# pinoccio-proto.net
KiCad netlist of a schematic drawn in EAGLE
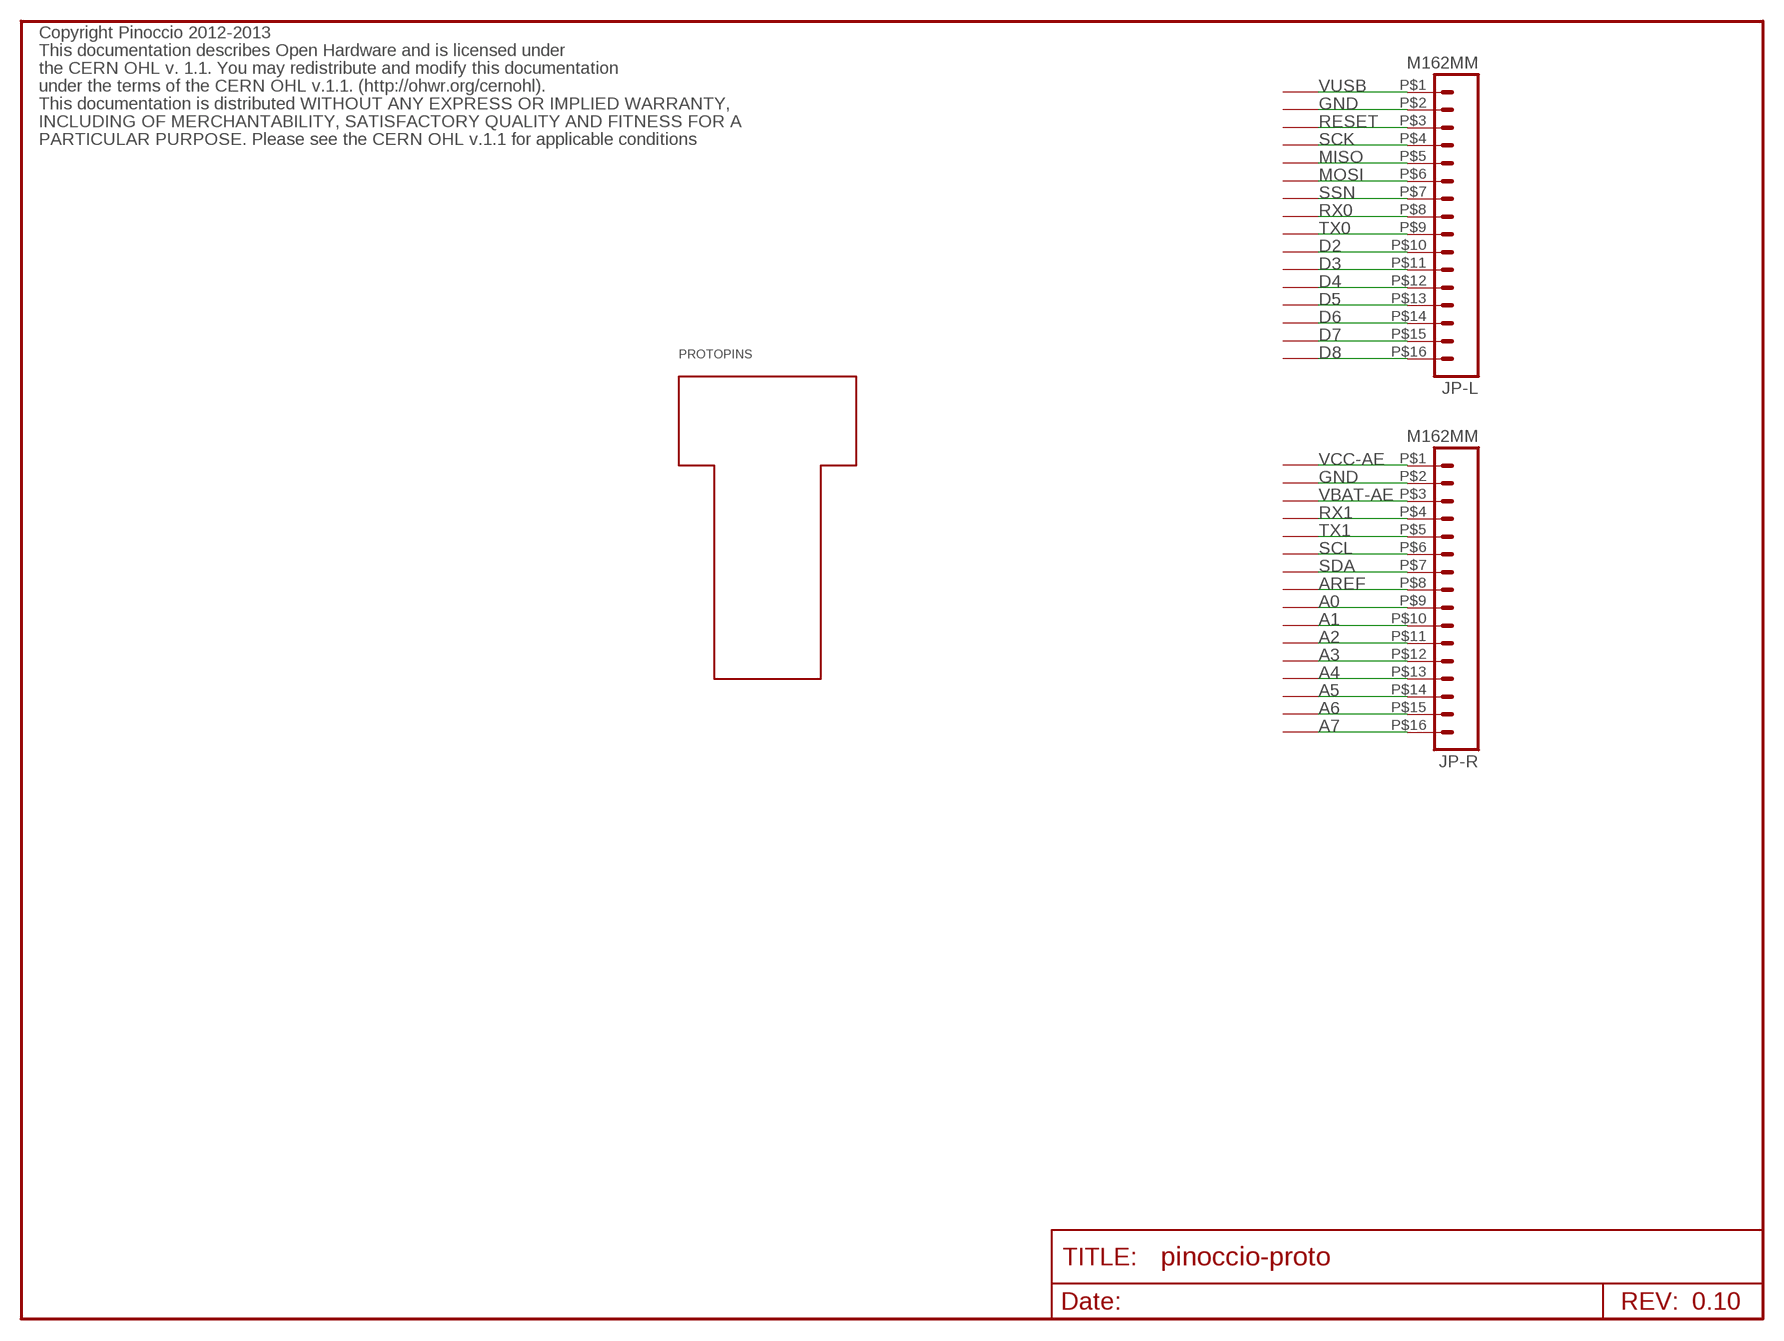
[diagram p0: schematic, sheet 1]

(export (version "E")
  (design (tool "Eeschema 10.0.6"))
  (components
    (comp (ref "JP-L")
      (value "M162MM")
      (footprint "eagle-import:1X16_2MM")
      (libsource (lib "eagle-import") (part "M162MM"))
    )
    (comp (ref "JP-R")
      (value "M162MM")
      (footprint "eagle-import:1X16_2MM")
      (libsource (lib "eagle-import") (part "M162MM"))
    )
    (comp (ref "PROTOPINS")
      (value "PROTO")
      (footprint "eagle-import:1X1PROTO")
      (libsource (lib "eagle-import") (part "PROTO"))
    )
    (comp (ref "U$2")
      (value "PAD55-RRECT")
      (footprint "eagle-import:PAD-100X55-RRECT")
      (libsource (lib "eagle-import") (part "PAD55-RRECT"))
    )
    (comp (ref "U$3")
      (value "PAD55-RRECT")
      (footprint "eagle-import:PAD-100X55-RRECT")
      (libsource (lib "eagle-import") (part "PAD55-RRECT"))
    )
    (comp (ref "U$4")
      (value "PAD55-RRECT")
      (footprint "eagle-import:PAD-100X55-RRECT")
      (libsource (lib "eagle-import") (part "PAD55-RRECT"))
    )
    (comp (ref "U$5")
      (value "PAD55-RRECT")
      (footprint "eagle-import:PAD-100X55-RRECT")
      (libsource (lib "eagle-import") (part "PAD55-RRECT"))
    )
    (comp (ref "U$6")
      (value "PAD55-RRECT")
      (footprint "eagle-import:PAD-100X55-RRECT")
      (libsource (lib "eagle-import") (part "PAD55-RRECT"))
    )
    (comp (ref "U$7")
      (value "PAD55-RRECT")
      (footprint "eagle-import:PAD-100X55-RRECT")
      (libsource (lib "eagle-import") (part "PAD55-RRECT"))
    )
    (comp (ref "U$8")
      (value "PAD55-RRECT")
      (footprint "eagle-import:PAD-100X55-RRECT")
      (libsource (lib "eagle-import") (part "PAD55-RRECT"))
    )
    (comp (ref "U$9")
      (value "PAD55-RRECT")
      (footprint "eagle-import:PAD-100X55-RRECT")
      (libsource (lib "eagle-import") (part "PAD55-RRECT"))
    )
    (comp (ref "U$10")
      (value "PAD55-RRECT")
      (footprint "eagle-import:PAD-100X55-RRECT")
      (libsource (lib "eagle-import") (part "PAD55-RRECT"))
    )
    (comp (ref "U$11")
      (value "PAD55-RRECT")
      (footprint "eagle-import:PAD-100X55-RRECT")
      (libsource (lib "eagle-import") (part "PAD55-RRECT"))
    )
    (comp (ref "U$12")
      (value "PAD55-RRECT")
      (footprint "eagle-import:PAD-100X55-RRECT")
      (libsource (lib "eagle-import") (part "PAD55-RRECT"))
    )
    (comp (ref "U$13")
      (value "PAD55-RRECT")
      (footprint "eagle-import:PAD-100X55-RRECT")
      (libsource (lib "eagle-import") (part "PAD55-RRECT"))
    )
    (comp (ref "U$14")
      (value "PAD55-RRECT")
      (footprint "eagle-import:PAD-100X55-RRECT")
      (libsource (lib "eagle-import") (part "PAD55-RRECT"))
    )
    (comp (ref "U$15")
      (value "PAD55-RRECT")
      (footprint "eagle-import:PAD-100X55-RRECT")
      (libsource (lib "eagle-import") (part "PAD55-RRECT"))
    )
    (comp (ref "U$16")
      (value "PAD55-RRECT")
      (footprint "eagle-import:PAD-100X55-RRECT")
      (libsource (lib "eagle-import") (part "PAD55-RRECT"))
    )
    (comp (ref "U$17")
      (value "PAD55-RRECT")
      (footprint "eagle-import:PAD-100X55-RRECT")
      (libsource (lib "eagle-import") (part "PAD55-RRECT"))
    )
    (comp (ref "U$18")
      (value "PAD55-RRECT")
      (footprint "eagle-import:PAD-100X55-RRECT")
      (libsource (lib "eagle-import") (part "PAD55-RRECT"))
    )
    (comp (ref "U$19")
      (value "PAD55-RRECT")
      (footprint "eagle-import:PAD-100X55-RRECT")
      (libsource (lib "eagle-import") (part "PAD55-RRECT"))
    )
    (comp (ref "U$20")
      (value "PAD55-RRECT")
      (footprint "eagle-import:PAD-100X55-RRECT")
      (libsource (lib "eagle-import") (part "PAD55-RRECT"))
    )
    (comp (ref "U$21")
      (value "PAD55-RRECT")
      (footprint "eagle-import:PAD-100X55-RRECT")
      (libsource (lib "eagle-import") (part "PAD55-RRECT"))
    )
    (comp (ref "U$22")
      (value "PAD55-RRECT")
      (footprint "eagle-import:PAD-100X55-RRECT")
      (libsource (lib "eagle-import") (part "PAD55-RRECT"))
    )
    (comp (ref "U$23")
      (value "PAD55-RRECT")
      (footprint "eagle-import:PAD-100X55-RRECT")
      (libsource (lib "eagle-import") (part "PAD55-RRECT"))
    )
    (comp (ref "U$24")
      (value "PAD55-RRECT")
      (footprint "eagle-import:PAD-100X55-RRECT")
      (libsource (lib "eagle-import") (part "PAD55-RRECT"))
    )
    (comp (ref "U$25")
      (value "PAD55-RRECT")
      (footprint "eagle-import:PAD-100X55-RRECT")
      (libsource (lib "eagle-import") (part "PAD55-RRECT"))
    )
    (comp (ref "U$26")
      (value "PAD55-RRECT")
      (footprint "eagle-import:PAD-100X55-RRECT")
      (libsource (lib "eagle-import") (part "PAD55-RRECT"))
    )
    (comp (ref "U$27")
      (value "PAD55-RRECT")
      (footprint "eagle-import:PAD-100X55-RRECT")
      (libsource (lib "eagle-import") (part "PAD55-RRECT"))
    )
    (comp (ref "U$28")
      (value "PAD55-RRECT")
      (footprint "eagle-import:PAD-100X55-RRECT")
      (libsource (lib "eagle-import") (part "PAD55-RRECT"))
    )
    (comp (ref "U$29")
      (value "PAD55-RRECT")
      (footprint "eagle-import:PAD-100X55-RRECT")
      (libsource (lib "eagle-import") (part "PAD55-RRECT"))
    )
    (comp (ref "U$30")
      (value "PAD55-RRECT")
      (footprint "eagle-import:PAD-100X55-RRECT")
      (libsource (lib "eagle-import") (part "PAD55-RRECT"))
    )
    (comp (ref "U$31")
      (value "PAD55-RRECT")
      (footprint "eagle-import:PAD-100X55-RRECT")
      (libsource (lib "eagle-import") (part "PAD55-RRECT"))
    )
    (comp (ref "U$32")
      (value "PAD55-RRECT")
      (footprint "eagle-import:PAD-100X55-RRECT")
      (libsource (lib "eagle-import") (part "PAD55-RRECT"))
    )
    (comp (ref "U$33")
      (value "PAD55-RRECT")
      (footprint "eagle-import:PAD-100X55-RRECT")
      (libsource (lib "eagle-import") (part "PAD55-RRECT"))
    )
  )
  (nets
    (net (code "1") (name "/A0") (class "Default")
      (node (ref "JP-R") (pin "P$9") (pinfunction "9_P$9") (pintype "passive"))
      (node (ref "U$25") (pin "P$1") (pinfunction "P$1_P$1") (pintype "bidirectional"))
    )
    (net (code "2") (name "/A1") (class "Default")
      (node (ref "JP-R") (pin "P$10") (pinfunction "10_P$10") (pintype "passive"))
      (node (ref "U$24") (pin "P$1") (pinfunction "P$1_P$1") (pintype "bidirectional"))
    )
    (net (code "3") (name "/A2") (class "Default")
      (node (ref "JP-R") (pin "P$11") (pinfunction "11_P$11") (pintype "passive"))
      (node (ref "U$23") (pin "P$1") (pinfunction "P$1_P$1") (pintype "bidirectional"))
    )
    (net (code "4") (name "/A3") (class "Default")
      (node (ref "JP-R") (pin "P$12") (pinfunction "12_P$12") (pintype "passive"))
      (node (ref "U$22") (pin "P$1") (pinfunction "P$1_P$1") (pintype "bidirectional"))
    )
    (net (code "5") (name "/A4") (class "Default")
      (node (ref "JP-R") (pin "P$13") (pinfunction "13_P$13") (pintype "passive"))
      (node (ref "U$21") (pin "P$1") (pinfunction "P$1_P$1") (pintype "bidirectional"))
    )
    (net (code "6") (name "/A5") (class "Default")
      (node (ref "JP-R") (pin "P$14") (pinfunction "14_P$14") (pintype "passive"))
      (node (ref "U$20") (pin "P$1") (pinfunction "P$1_P$1") (pintype "bidirectional"))
    )
    (net (code "7") (name "/A6") (class "Default")
      (node (ref "JP-R") (pin "P$15") (pinfunction "15_P$15") (pintype "passive"))
      (node (ref "U$19") (pin "P$1") (pinfunction "P$1_P$1") (pintype "bidirectional"))
    )
    (net (code "8") (name "/A7") (class "Default")
      (node (ref "JP-R") (pin "P$16") (pinfunction "16_P$16") (pintype "passive"))
      (node (ref "U$18") (pin "P$1") (pinfunction "P$1_P$1") (pintype "bidirectional"))
    )
    (net (code "9") (name "/AREF") (class "Default")
      (node (ref "JP-R") (pin "P$8") (pinfunction "8_P$8") (pintype "passive"))
      (node (ref "U$26") (pin "P$1") (pinfunction "P$1_P$1") (pintype "bidirectional"))
    )
    (net (code "10") (name "/D2") (class "Default")
      (node (ref "JP-L") (pin "P$10") (pinfunction "10_P$10") (pintype "passive"))
      (node (ref "U$7") (pin "P$1") (pinfunction "P$1_P$1") (pintype "bidirectional"))
    )
    (net (code "11") (name "/D3") (class "Default")
      (node (ref "JP-L") (pin "P$11") (pinfunction "11_P$11") (pintype "passive"))
      (node (ref "U$6") (pin "P$1") (pinfunction "P$1_P$1") (pintype "bidirectional"))
    )
    (net (code "12") (name "/D4") (class "Default")
      (node (ref "JP-L") (pin "P$12") (pinfunction "12_P$12") (pintype "passive"))
      (node (ref "U$5") (pin "P$1") (pinfunction "P$1_P$1") (pintype "bidirectional"))
    )
    (net (code "13") (name "/D5") (class "Default")
      (node (ref "JP-L") (pin "P$13") (pinfunction "13_P$13") (pintype "passive"))
      (node (ref "U$3") (pin "P$1") (pinfunction "P$1_P$1") (pintype "bidirectional"))
    )
    (net (code "14") (name "/D6") (class "Default")
      (node (ref "JP-L") (pin "P$14") (pinfunction "14_P$14") (pintype "passive"))
      (node (ref "U$4") (pin "P$1") (pinfunction "P$1_P$1") (pintype "bidirectional"))
    )
    (net (code "15") (name "/D7") (class "Default")
      (node (ref "JP-L") (pin "P$15") (pinfunction "15_P$15") (pintype "passive"))
      (node (ref "U$2") (pin "P$1") (pinfunction "P$1_P$1") (pintype "bidirectional"))
    )
    (net (code "16") (name "/D8") (class "Default")
      (node (ref "JP-L") (pin "P$16") (pinfunction "16_P$16") (pintype "passive"))
      (node (ref "U$17") (pin "P$1") (pinfunction "P$1_P$1") (pintype "bidirectional"))
    )
    (net (code "17") (name "/GND") (class "Default")
      (node (ref "JP-L") (pin "P$2") (pinfunction "2_P$2") (pintype "passive"))
      (node (ref "JP-R") (pin "P$2") (pinfunction "2_P$2") (pintype "passive"))
      (node (ref "U$15") (pin "P$1") (pinfunction "P$1_P$1") (pintype "bidirectional"))
      (node (ref "U$32") (pin "P$1") (pinfunction "P$1_P$1") (pintype "bidirectional"))
    )
    (net (code "18") (name "/MISO") (class "Default")
      (node (ref "JP-L") (pin "P$5") (pinfunction "5_P$5") (pintype "passive"))
      (node (ref "U$12") (pin "P$1") (pinfunction "P$1_P$1") (pintype "bidirectional"))
    )
    (net (code "19") (name "/MOSI") (class "Default")
      (node (ref "JP-L") (pin "P$6") (pinfunction "6_P$6") (pintype "passive"))
      (node (ref "U$11") (pin "P$1") (pinfunction "P$1_P$1") (pintype "bidirectional"))
    )
    (net (code "20") (name "/RESET") (class "Default")
      (node (ref "JP-L") (pin "P$3") (pinfunction "3_P$3") (pintype "passive"))
      (node (ref "U$14") (pin "P$1") (pinfunction "P$1_P$1") (pintype "bidirectional"))
    )
    (net (code "21") (name "/RX0") (class "Default")
      (node (ref "JP-L") (pin "P$8") (pinfunction "8_P$8") (pintype "passive"))
      (node (ref "U$9") (pin "P$1") (pinfunction "P$1_P$1") (pintype "bidirectional"))
    )
    (net (code "22") (name "/RX1") (class "Default")
      (node (ref "JP-R") (pin "P$4") (pinfunction "4_P$4") (pintype "passive"))
      (node (ref "U$30") (pin "P$1") (pinfunction "P$1_P$1") (pintype "bidirectional"))
    )
    (net (code "23") (name "/SCK") (class "Default")
      (node (ref "JP-L") (pin "P$4") (pinfunction "4_P$4") (pintype "passive"))
      (node (ref "U$13") (pin "P$1") (pinfunction "P$1_P$1") (pintype "bidirectional"))
    )
    (net (code "24") (name "/SCL") (class "Default")
      (node (ref "JP-R") (pin "P$6") (pinfunction "6_P$6") (pintype "passive"))
      (node (ref "U$28") (pin "P$1") (pinfunction "P$1_P$1") (pintype "bidirectional"))
    )
    (net (code "25") (name "/SDA") (class "Default")
      (node (ref "JP-R") (pin "P$7") (pinfunction "7_P$7") (pintype "passive"))
      (node (ref "U$27") (pin "P$1") (pinfunction "P$1_P$1") (pintype "bidirectional"))
    )
    (net (code "26") (name "/SSN") (class "Default")
      (node (ref "JP-L") (pin "P$7") (pinfunction "7_P$7") (pintype "passive"))
      (node (ref "U$10") (pin "P$1") (pinfunction "P$1_P$1") (pintype "bidirectional"))
    )
    (net (code "27") (name "/TX0") (class "Default")
      (node (ref "JP-L") (pin "P$9") (pinfunction "9_P$9") (pintype "passive"))
      (node (ref "U$8") (pin "P$1") (pinfunction "P$1_P$1") (pintype "bidirectional"))
    )
    (net (code "28") (name "/TX1") (class "Default")
      (node (ref "JP-R") (pin "P$5") (pinfunction "5_P$5") (pintype "passive"))
      (node (ref "U$29") (pin "P$1") (pinfunction "P$1_P$1") (pintype "bidirectional"))
    )
    (net (code "29") (name "/VBAT-AE") (class "Default")
      (node (ref "JP-R") (pin "P$3") (pinfunction "3_P$3") (pintype "passive"))
      (node (ref "U$31") (pin "P$1") (pinfunction "P$1_P$1") (pintype "bidirectional"))
    )
    (net (code "30") (name "/VCC-AE") (class "Default")
      (node (ref "JP-R") (pin "P$1") (pinfunction "1_P$1") (pintype "passive"))
      (node (ref "U$33") (pin "P$1") (pinfunction "P$1_P$1") (pintype "bidirectional"))
    )
    (net (code "31") (name "/VUSB") (class "Default")
      (node (ref "JP-L") (pin "P$1") (pinfunction "1_P$1") (pintype "passive"))
      (node (ref "U$16") (pin "P$1") (pinfunction "P$1_P$1") (pintype "bidirectional"))
    )
    (net (code "32") (name "unconnected-(PROTOPINS-P$1-Pad0)") (class "Default")
      (node (ref "PROTOPINS") (pin "0") (pinfunction "P$1_0") (pintype "bidirectional"))
    )
    (net (code "33") (name "unconnected-(PROTOPINS-P$2-Pad1)") (class "Default")
      (node (ref "PROTOPINS") (pin "1") (pinfunction "P$2_1") (pintype "bidirectional"))
    )
    (net (code "34") (name "unconnected-(PROTOPINS-P$3-Pad2)") (class "Default")
      (node (ref "PROTOPINS") (pin "2") (pinfunction "P$3_2") (pintype "bidirectional"))
    )
    (net (code "35") (name "unconnected-(PROTOPINS-P$4-Pad3)") (class "Default")
      (node (ref "PROTOPINS") (pin "3") (pinfunction "P$4_3") (pintype "bidirectional"))
    )
    (net (code "36") (name "unconnected-(PROTOPINS-P$5-Pad4)") (class "Default")
      (node (ref "PROTOPINS") (pin "4") (pinfunction "P$5_4") (pintype "bidirectional"))
    )
    (net (code "37") (name "unconnected-(PROTOPINS-P$6-Pad6)") (class "Default")
      (node (ref "PROTOPINS") (pin "6") (pinfunction "P$6_6") (pintype "bidirectional"))
    )
    (net (code "38") (name "unconnected-(PROTOPINS-P$7-Pad7)") (class "Default")
      (node (ref "PROTOPINS") (pin "7") (pinfunction "P$7_7") (pintype "bidirectional"))
    )
    (net (code "39") (name "unconnected-(PROTOPINS-P$8-Pad8)") (class "Default")
      (node (ref "PROTOPINS") (pin "8") (pinfunction "P$8_8") (pintype "bidirectional"))
    )
    (net (code "40") (name "unconnected-(PROTOPINS-P$9-Pad9)") (class "Default")
      (node (ref "PROTOPINS") (pin "9") (pinfunction "P$9_9") (pintype "bidirectional"))
    )
    (net (code "41") (name "unconnected-(PROTOPINS-P$10-Pad10)") (class "Default")
      (node (ref "PROTOPINS") (pin "10") (pinfunction "P$10_10") (pintype "bidirectional"))
    )
    (net (code "42") (name "unconnected-(PROTOPINS-P$11-Pad11)") (class "Default")
      (node (ref "PROTOPINS") (pin "11") (pinfunction "P$11_11") (pintype "bidirectional"))
    )
    (net (code "43") (name "unconnected-(PROTOPINS-P$12-Pad12)") (class "Default")
      (node (ref "PROTOPINS") (pin "12") (pinfunction "P$12_12") (pintype "bidirectional"))
    )
    (net (code "44") (name "unconnected-(PROTOPINS-P$13-Pad13)") (class "Default")
      (node (ref "PROTOPINS") (pin "13") (pinfunction "P$13_13") (pintype "bidirectional"))
    )
    (net (code "45") (name "unconnected-(PROTOPINS-P$14-Pad14)") (class "Default")
      (node (ref "PROTOPINS") (pin "14") (pinfunction "P$14_14") (pintype "bidirectional"))
    )
    (net (code "46") (name "unconnected-(PROTOPINS-P$15-Pad15)") (class "Default")
      (node (ref "PROTOPINS") (pin "15") (pinfunction "P$15_15") (pintype "bidirectional"))
    )
    (net (code "47") (name "unconnected-(PROTOPINS-P$16-Pad16)") (class "Default")
      (node (ref "PROTOPINS") (pin "16") (pinfunction "P$16_16") (pintype "bidirectional"))
    )
    (net (code "48") (name "unconnected-(PROTOPINS-P$17-Pad17)") (class "Default")
      (node (ref "PROTOPINS") (pin "17") (pinfunction "P$17_17") (pintype "bidirectional"))
    )
    (net (code "49") (name "unconnected-(PROTOPINS-P$18-Pad18)") (class "Default")
      (node (ref "PROTOPINS") (pin "18") (pinfunction "P$18_18") (pintype "bidirectional"))
    )
    (net (code "50") (name "unconnected-(PROTOPINS-P$19-Pad19)") (class "Default")
      (node (ref "PROTOPINS") (pin "19") (pinfunction "P$19_19") (pintype "bidirectional"))
    )
    (net (code "51") (name "unconnected-(PROTOPINS-P$20-Pad20)") (class "Default")
      (node (ref "PROTOPINS") (pin "20") (pinfunction "P$20_20") (pintype "bidirectional"))
    )
    (net (code "52") (name "unconnected-(PROTOPINS-P$21-Pad21)") (class "Default")
      (node (ref "PROTOPINS") (pin "21") (pinfunction "P$21_21") (pintype "bidirectional"))
    )
    (net (code "53") (name "unconnected-(PROTOPINS-P$22-Pad22)") (class "Default")
      (node (ref "PROTOPINS") (pin "22") (pinfunction "P$22_22") (pintype "bidirectional"))
    )
    (net (code "54") (name "unconnected-(PROTOPINS-P$23-Pad23)") (class "Default")
      (node (ref "PROTOPINS") (pin "23") (pinfunction "P$23_23") (pintype "bidirectional"))
    )
    (net (code "55") (name "unconnected-(PROTOPINS-P$24-Pad24)") (class "Default")
      (node (ref "PROTOPINS") (pin "24") (pinfunction "P$24_24") (pintype "bidirectional"))
    )
    (net (code "56") (name "unconnected-(PROTOPINS-P$25-Pad25)") (class "Default")
      (node (ref "PROTOPINS") (pin "25") (pinfunction "P$25_25") (pintype "bidirectional"))
    )
    (net (code "57") (name "unconnected-(PROTOPINS-P$26-Pad26)") (class "Default")
      (node (ref "PROTOPINS") (pin "26") (pinfunction "P$26_26") (pintype "bidirectional"))
    )
    (net (code "58") (name "unconnected-(PROTOPINS-P$27-Pad27)") (class "Default")
      (node (ref "PROTOPINS") (pin "27") (pinfunction "P$27_27") (pintype "bidirectional"))
    )
    (net (code "59") (name "unconnected-(PROTOPINS-P$28-Pad28)") (class "Default")
      (node (ref "PROTOPINS") (pin "28") (pinfunction "P$28_28") (pintype "bidirectional"))
    )
    (net (code "60") (name "unconnected-(PROTOPINS-P$29-Pad29)") (class "Default")
      (node (ref "PROTOPINS") (pin "29") (pinfunction "P$29_29") (pintype "bidirectional"))
    )
    (net (code "61") (name "unconnected-(PROTOPINS-P$30-Pad30)") (class "Default")
      (node (ref "PROTOPINS") (pin "30") (pinfunction "P$30_30") (pintype "bidirectional"))
    )
    (net (code "62") (name "unconnected-(PROTOPINS-P$31-Pad31)") (class "Default")
      (node (ref "PROTOPINS") (pin "31") (pinfunction "P$31_31") (pintype "bidirectional"))
    )
    (net (code "63") (name "unconnected-(PROTOPINS-P$32-Pad32)") (class "Default")
      (node (ref "PROTOPINS") (pin "32") (pinfunction "P$32_32") (pintype "bidirectional"))
    )
    (net (code "64") (name "unconnected-(PROTOPINS-P$33-Pad33)") (class "Default")
      (node (ref "PROTOPINS") (pin "33") (pinfunction "P$33_33") (pintype "bidirectional"))
    )
    (net (code "65") (name "unconnected-(PROTOPINS-P$34-Pad34)") (class "Default")
      (node (ref "PROTOPINS") (pin "34") (pinfunction "P$34_34") (pintype "bidirectional"))
    )
    (net (code "66") (name "unconnected-(PROTOPINS-P$35-Pad35)") (class "Default")
      (node (ref "PROTOPINS") (pin "35") (pinfunction "P$35_35") (pintype "bidirectional"))
    )
    (net (code "67") (name "unconnected-(PROTOPINS-P$36-Pad36)") (class "Default")
      (node (ref "PROTOPINS") (pin "36") (pinfunction "P$36_36") (pintype "bidirectional"))
    )
    (net (code "68") (name "unconnected-(PROTOPINS-P$37-Pad37)") (class "Default")
      (node (ref "PROTOPINS") (pin "37") (pinfunction "P$37_37") (pintype "bidirectional"))
    )
    (net (code "69") (name "unconnected-(PROTOPINS-P$38-Pad38)") (class "Default")
      (node (ref "PROTOPINS") (pin "38") (pinfunction "P$38_38") (pintype "bidirectional"))
    )
    (net (code "70") (name "unconnected-(PROTOPINS-P$39-Pad39)") (class "Default")
      (node (ref "PROTOPINS") (pin "39") (pinfunction "P$39_39") (pintype "bidirectional"))
    )
    (net (code "71") (name "unconnected-(PROTOPINS-P$40-Pad40)") (class "Default")
      (node (ref "PROTOPINS") (pin "40") (pinfunction "P$40_40") (pintype "bidirectional"))
    )
    (net (code "72") (name "unconnected-(PROTOPINS-P$41-Pad41)") (class "Default")
      (node (ref "PROTOPINS") (pin "41") (pinfunction "P$41_41") (pintype "bidirectional"))
    )
    (net (code "73") (name "unconnected-(PROTOPINS-P$42-Pad42)") (class "Default")
      (node (ref "PROTOPINS") (pin "42") (pinfunction "P$42_42") (pintype "bidirectional"))
    )
    (net (code "74") (name "unconnected-(PROTOPINS-P$43-Pad43)") (class "Default")
      (node (ref "PROTOPINS") (pin "43") (pinfunction "P$43_43") (pintype "bidirectional"))
    )
    (net (code "75") (name "unconnected-(PROTOPINS-P$44-Pad44)") (class "Default")
      (node (ref "PROTOPINS") (pin "44") (pinfunction "P$44_44") (pintype "bidirectional"))
    )
    (net (code "76") (name "unconnected-(PROTOPINS-P$45-Pad45)") (class "Default")
      (node (ref "PROTOPINS") (pin "45") (pinfunction "P$45_45") (pintype "bidirectional"))
    )
    (net (code "77") (name "unconnected-(PROTOPINS-P$46-Pad46)") (class "Default")
      (node (ref "PROTOPINS") (pin "46") (pinfunction "P$46_46") (pintype "bidirectional"))
    )
    (net (code "78") (name "unconnected-(PROTOPINS-P$47-Pad47)") (class "Default")
      (node (ref "PROTOPINS") (pin "47") (pinfunction "P$47_47") (pintype "bidirectional"))
    )
    (net (code "79") (name "unconnected-(PROTOPINS-P$48-Pad48)") (class "Default")
      (node (ref "PROTOPINS") (pin "48") (pinfunction "P$48_48") (pintype "bidirectional"))
    )
    (net (code "80") (name "unconnected-(PROTOPINS-P$49-Pad49)") (class "Default")
      (node (ref "PROTOPINS") (pin "49") (pinfunction "P$49_49") (pintype "bidirectional"))
    )
    (net (code "81") (name "unconnected-(PROTOPINS-P$50-Pad50)") (class "Default")
      (node (ref "PROTOPINS") (pin "50") (pinfunction "P$50_50") (pintype "bidirectional"))
    )
    (net (code "82") (name "unconnected-(PROTOPINS-P$51-Pad51)") (class "Default")
      (node (ref "PROTOPINS") (pin "51") (pinfunction "P$51_51") (pintype "bidirectional"))
    )
    (net (code "83") (name "unconnected-(PROTOPINS-P$52-Pad52)") (class "Default")
      (node (ref "PROTOPINS") (pin "52") (pinfunction "P$52_52") (pintype "bidirectional"))
    )
    (net (code "84") (name "unconnected-(PROTOPINS-P$53-Pad53)") (class "Default")
      (node (ref "PROTOPINS") (pin "53") (pinfunction "P$53_53") (pintype "bidirectional"))
    )
    (net (code "85") (name "unconnected-(PROTOPINS-P$54-Pad54)") (class "Default")
      (node (ref "PROTOPINS") (pin "54") (pinfunction "P$54_54") (pintype "bidirectional"))
    )
    (net (code "86") (name "unconnected-(PROTOPINS-P$55-Pad55)") (class "Default")
      (node (ref "PROTOPINS") (pin "55") (pinfunction "P$55_55") (pintype "bidirectional"))
    )
    (net (code "87") (name "unconnected-(PROTOPINS-P$56-Pad56)") (class "Default")
      (node (ref "PROTOPINS") (pin "56") (pinfunction "P$56_56") (pintype "bidirectional"))
    )
    (net (code "88") (name "unconnected-(PROTOPINS-P$57-Pad57)") (class "Default")
      (node (ref "PROTOPINS") (pin "57") (pinfunction "P$57_57") (pintype "bidirectional"))
    )
    (net (code "89") (name "unconnected-(PROTOPINS-P$58-Pad58)") (class "Default")
      (node (ref "PROTOPINS") (pin "58") (pinfunction "P$58_58") (pintype "bidirectional"))
    )
    (net (code "90") (name "unconnected-(PROTOPINS-P$59-Pad59)") (class "Default")
      (node (ref "PROTOPINS") (pin "59") (pinfunction "P$59_59") (pintype "bidirectional"))
    )
    (net (code "91") (name "unconnected-(PROTOPINS-P$60-Pad60)") (class "Default")
      (node (ref "PROTOPINS") (pin "60") (pinfunction "P$60_60") (pintype "bidirectional"))
    )
    (net (code "92") (name "unconnected-(PROTOPINS-P$61-Pad61)") (class "Default")
      (node (ref "PROTOPINS") (pin "61") (pinfunction "P$61_61") (pintype "bidirectional"))
    )
    (net (code "93") (name "unconnected-(PROTOPINS-P$62-Pad62)") (class "Default")
      (node (ref "PROTOPINS") (pin "62") (pinfunction "P$62_62") (pintype "bidirectional"))
    )
    (net (code "94") (name "unconnected-(PROTOPINS-P$63-Pad63)") (class "Default")
      (node (ref "PROTOPINS") (pin "63") (pinfunction "P$63_63") (pintype "bidirectional"))
    )
    (net (code "95") (name "unconnected-(PROTOPINS-P$64-Pad64)") (class "Default")
      (node (ref "PROTOPINS") (pin "64") (pinfunction "P$64_64") (pintype "bidirectional"))
    )
    (net (code "96") (name "unconnected-(PROTOPINS-P$65-Pad65)") (class "Default")
      (node (ref "PROTOPINS") (pin "65") (pinfunction "P$65_65") (pintype "bidirectional"))
    )
    (net (code "97") (name "unconnected-(PROTOPINS-P$66-Pad66)") (class "Default")
      (node (ref "PROTOPINS") (pin "66") (pinfunction "P$66_66") (pintype "bidirectional"))
    )
    (net (code "98") (name "unconnected-(PROTOPINS-P$67-Pad67)") (class "Default")
      (node (ref "PROTOPINS") (pin "67") (pinfunction "P$67_67") (pintype "bidirectional"))
    )
    (net (code "99") (name "unconnected-(PROTOPINS-P$68-Pad68)") (class "Default")
      (node (ref "PROTOPINS") (pin "68") (pinfunction "P$68_68") (pintype "bidirectional"))
    )
    (net (code "100") (name "unconnected-(PROTOPINS-P$69-Pad69)") (class "Default")
      (node (ref "PROTOPINS") (pin "69") (pinfunction "P$69_69") (pintype "bidirectional"))
    )
    (net (code "101") (name "unconnected-(PROTOPINS-P$70-Pad70)") (class "Default")
      (node (ref "PROTOPINS") (pin "70") (pinfunction "P$70_70") (pintype "bidirectional"))
    )
    (net (code "102") (name "unconnected-(PROTOPINS-P$71-Pad5)") (class "Default")
      (node (ref "PROTOPINS") (pin "5") (pinfunction "P$71_5") (pintype "bidirectional"))
    )
    (net (code "103") (name "unconnected-(PROTOPINS-P$72-Pad71)") (class "Default")
      (node (ref "PROTOPINS") (pin "71") (pinfunction "P$72_71") (pintype "bidirectional"))
    )
    (net (code "104") (name "unconnected-(PROTOPINS-P$73-Pad74)") (class "Default")
      (node (ref "PROTOPINS") (pin "74") (pinfunction "P$73_74") (pintype "bidirectional"))
    )
    (net (code "105") (name "unconnected-(PROTOPINS-P$75-Pad75)") (class "Default")
      (node (ref "PROTOPINS") (pin "75") (pinfunction "P$75_75") (pintype "bidirectional"))
    )
    (net (code "106") (name "unconnected-(PROTOPINS-P$76-Pad76)") (class "Default")
      (node (ref "PROTOPINS") (pin "76") (pinfunction "P$76_76") (pintype "bidirectional"))
    )
    (net (code "107") (name "unconnected-(PROTOPINS-P$77-Pad77)") (class "Default")
      (node (ref "PROTOPINS") (pin "77") (pinfunction "P$77_77") (pintype "bidirectional"))
    )
    (net (code "108") (name "unconnected-(PROTOPINS-P$78-Pad78)") (class "Default")
      (node (ref "PROTOPINS") (pin "78") (pinfunction "P$78_78") (pintype "bidirectional"))
    )
    (net (code "109") (name "unconnected-(PROTOPINS-P$79-Pad79)") (class "Default")
      (node (ref "PROTOPINS") (pin "79") (pinfunction "P$79_79") (pintype "bidirectional"))
    )
    (net (code "110") (name "unconnected-(PROTOPINS-P$81-Pad80)") (class "Default")
      (node (ref "PROTOPINS") (pin "80") (pinfunction "P$81_80") (pintype "bidirectional"))
    )
    (net (code "111") (name "unconnected-(PROTOPINS-P$82-Pad83)") (class "Default")
      (node (ref "PROTOPINS") (pin "83") (pinfunction "P$82_83") (pintype "bidirectional"))
    )
    (net (code "112") (name "unconnected-(PROTOPINS-P$84-Pad84)") (class "Default")
      (node (ref "PROTOPINS") (pin "84") (pinfunction "P$84_84") (pintype "bidirectional"))
    )
    (net (code "113") (name "unconnected-(PROTOPINS-P$85-Pad85)") (class "Default")
      (node (ref "PROTOPINS") (pin "85") (pinfunction "P$85_85") (pintype "bidirectional"))
    )
    (net (code "114") (name "unconnected-(PROTOPINS-P$86-Pad86)") (class "Default")
      (node (ref "PROTOPINS") (pin "86") (pinfunction "P$86_86") (pintype "bidirectional"))
    )
    (net (code "115") (name "unconnected-(PROTOPINS-P$87-Pad87)") (class "Default")
      (node (ref "PROTOPINS") (pin "87") (pinfunction "P$87_87") (pintype "bidirectional"))
    )
    (net (code "116") (name "unconnected-(PROTOPINS-P$88-Pad88)") (class "Default")
      (node (ref "PROTOPINS") (pin "88") (pinfunction "P$88_88") (pintype "bidirectional"))
    )
    (net (code "117") (name "unconnected-(PROTOPINS-P$90-Pad89)") (class "Default")
      (node (ref "PROTOPINS") (pin "89") (pinfunction "P$90_89") (pintype "bidirectional"))
    )
    (net (code "118") (name "unconnected-(PROTOPINS-P$91-Pad92)") (class "Default")
      (node (ref "PROTOPINS") (pin "92") (pinfunction "P$91_92") (pintype "bidirectional"))
    )
    (net (code "119") (name "unconnected-(PROTOPINS-P$93-Pad93)") (class "Default")
      (node (ref "PROTOPINS") (pin "93") (pinfunction "P$93_93") (pintype "bidirectional"))
    )
    (net (code "120") (name "unconnected-(PROTOPINS-P$94-Pad94)") (class "Default")
      (node (ref "PROTOPINS") (pin "94") (pinfunction "P$94_94") (pintype "bidirectional"))
    )
    (net (code "121") (name "unconnected-(PROTOPINS-P$95-Pad95)") (class "Default")
      (node (ref "PROTOPINS") (pin "95") (pinfunction "P$95_95") (pintype "bidirectional"))
    )
    (net (code "122") (name "unconnected-(PROTOPINS-P$96-Pad96)") (class "Default")
      (node (ref "PROTOPINS") (pin "96") (pinfunction "P$96_96") (pintype "bidirectional"))
    )
    (net (code "123") (name "unconnected-(PROTOPINS-P$97-Pad97)") (class "Default")
      (node (ref "PROTOPINS") (pin "97") (pinfunction "P$97_97") (pintype "bidirectional"))
    )
    (net (code "124") (name "unconnected-(PROTOPINS-P$98-Pad98)") (class "Default")
      (node (ref "PROTOPINS") (pin "98") (pinfunction "P$98_98") (pintype "bidirectional"))
    )
    (net (code "125") (name "unconnected-(PROTOPINS-P$99-Pad99)") (class "Default")
      (node (ref "PROTOPINS") (pin "99") (pinfunction "P$99_99") (pintype "bidirectional"))
    )
    (net (code "126") (name "unconnected-(PROTOPINS-P$100-Pad100)") (class "Default")
      (node (ref "PROTOPINS") (pin "100") (pinfunction "P$100_100") (pintype "bidirectional"))
    )
    (net (code "127") (name "unconnected-(PROTOPINS-P$101-Pad101)") (class "Default")
      (node (ref "PROTOPINS") (pin "101") (pinfunction "P$101_101") (pintype "bidirectional"))
    )
  )
)
